# Communication_Interfaces.net
KiCad netlist of a schematic drawn in Altium Designer
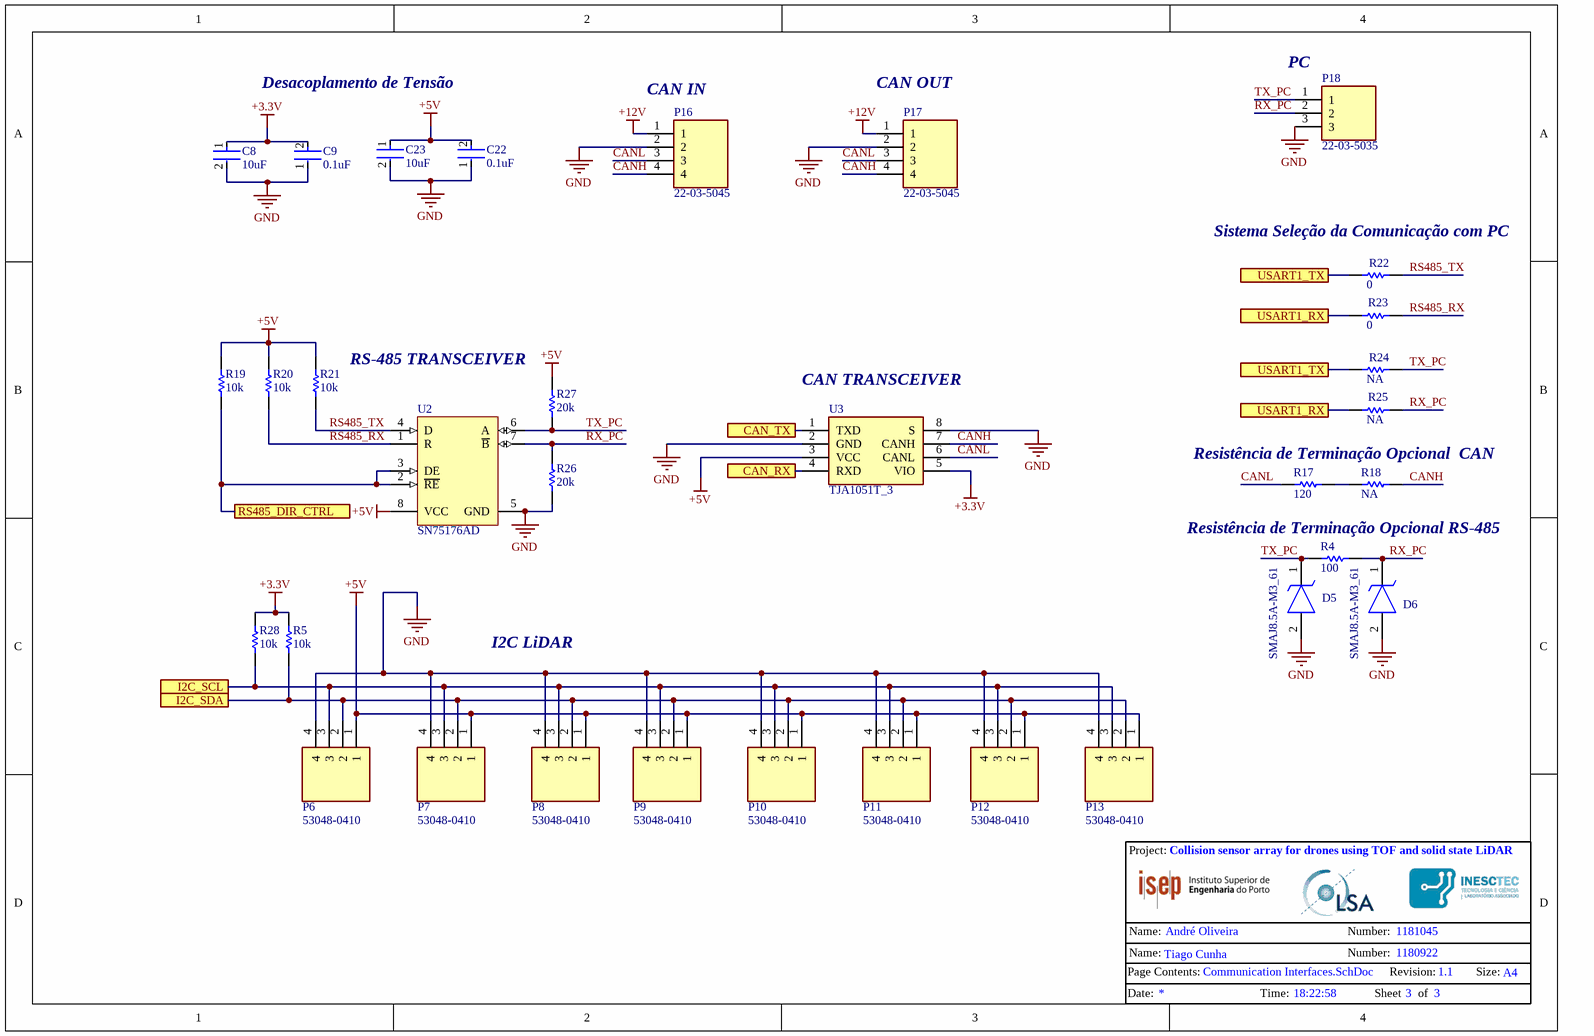
[diagram p0: Communication Interfaces.SchDoc]

(export (version "E")
  (design (tool "Eeschema 10.0.6"))
  (components
    (comp (ref "C8")
      (value "10uF")
      (footprint "FP-C3216-160-0_2-IPC_C")
      (description "Multilayer Ceramic Capacitors 10uF ±10% 16V X5R SMD 1206")
      (fields (field (name "VOLTAGE") "16V") (field (name "TOLERANCE") "10%"))
      (libsource (lib "Altium Content Vault") (part "11868f565c42a9108669ba33697ecf6"))
    )
    (comp (ref "C9")
      (value "0.1uF")
      (footprint "FP-GRM15-MFG")
      (description "CAP CER 0.1UF 16V X7R 0402")
      (fields (field (name "MANUFACTURER PART NUMBER") "GRM155R71C104KA88D") (field (name "TOLERANCE") "10%"))
      (libsource (lib "Altium Content Vault") (part "236180d848d6139a670b325ea6854c9"))
    )
    (comp (ref "C22")
      (value "0.1uF")
      (footprint "FP-GRM15-MFG")
      (description "CAP CER 0.1UF 16V X7R 0402")
      (fields (field (name "MANUFACTURER PART NUMBER") "GRM155R71C104KA88D") (field (name "TOLERANCE") "10%"))
      (libsource (lib "Altium Content Vault") (part "236180d848d6139a670b325ea6854c9"))
    )
    (comp (ref "C23")
      (value "10uF")
      (footprint "FP-C3216-160-0_2-IPC_C")
      (description "Multilayer Ceramic Capacitors 10uF ±10% 16V X5R SMD 1206")
      (fields (field (name "VOLTAGE") "16V") (field (name "TOLERANCE") "10%"))
      (libsource (lib "Altium Content Vault") (part "11868f565c42a9108669ba33697ecf6"))
    )
    (comp (ref "D5")
      (value "SMAJ8.5A-M3_61")
      (footprint "SamacSys:DIOM5127X229N")
      (description "TVS Diode (Uni-directional)")
      (fields (field (name "MANUFACTURER_PART_NUMBER") "SMAJ8.5A-M3/61"))
      (libsource (lib "*") (part "SMAJ8.5A-M3_61"))
    )
    (comp (ref "D6")
      (value "SMAJ8.5A-M3_61")
      (footprint "SamacSys:DIOM5127X229N")
      (description "TVS Diode (Uni-directional)")
      (fields (field (name "MANUFACTURER_PART_NUMBER") "SMAJ8.5A-M3/61"))
      (libsource (lib "*") (part "SMAJ8.5A-M3_61"))
    )
    (comp (ref "P6")
      (value "53048-0410")
      (footprint "SamacSys:530480410")
      (description "Connector")
      (fields (field (name "MOUSER PART NUMBER") "538-53048-0410"))
      (libsource (lib "*") (part "53048-0410"))
    )
    (comp (ref "P7")
      (value "53048-0410")
      (footprint "SamacSys:530480410")
      (description "Connector")
      (fields (field (name "MOUSER PART NUMBER") "538-53048-0410"))
      (libsource (lib "*") (part "53048-0410"))
    )
    (comp (ref "P8")
      (value "53048-0410")
      (footprint "SamacSys:530480410")
      (description "Connector")
      (fields (field (name "MOUSER PART NUMBER") "538-53048-0410"))
      (libsource (lib "*") (part "53048-0410"))
    )
    (comp (ref "P9")
      (value "53048-0410")
      (footprint "SamacSys:530480410")
      (description "Connector")
      (fields (field (name "MOUSER PART NUMBER") "538-53048-0410"))
      (libsource (lib "*") (part "53048-0410"))
    )
    (comp (ref "P10")
      (value "53048-0410")
      (footprint "SamacSys:530480410")
      (description "Connector")
      (fields (field (name "MOUSER PART NUMBER") "538-53048-0410"))
      (libsource (lib "*") (part "53048-0410"))
    )
    (comp (ref "P11")
      (value "53048-0410")
      (footprint "SamacSys:530480410")
      (description "Connector")
      (fields (field (name "MOUSER PART NUMBER") "538-53048-0410"))
      (libsource (lib "*") (part "53048-0410"))
    )
    (comp (ref "P12")
      (value "53048-0410")
      (footprint "SamacSys:530480410")
      (description "Connector")
      (fields (field (name "MOUSER PART NUMBER") "538-53048-0410"))
      (libsource (lib "*") (part "53048-0410"))
    )
    (comp (ref "P13")
      (value "53048-0410")
      (footprint "SamacSys:530480410")
      (description "Connector")
      (fields (field (name "MOUSER PART NUMBER") "538-53048-0410"))
      (libsource (lib "*") (part "53048-0410"))
    )
    (comp (ref "P16")
      (value "22-03-5045")
      (footprint "SamacSys:SHDR4W70P0X250_1X4_1240X490X610P")
      (description "Connector")
      (fields (field (name "MOUSER PART NUMBER") "538-22-03-5045"))
      (libsource (lib "*") (part "22-03-5045"))
    )
    (comp (ref "P17")
      (value "22-03-5045")
      (footprint "SamacSys:SHDR4W70P0X250_1X4_1240X490X610P")
      (description "Connector")
      (fields (field (name "MOUSER PART NUMBER") "538-22-03-5045"))
      (libsource (lib "*") (part "22-03-5045"))
    )
    (comp (ref "P18")
      (value "22-03-5035")
      (footprint "SamacSys:SHDR3W60P0X250_1X3_990X490X590P")
      (description "Connector")
      (fields (field (name "MOUSER PART NUMBER") "538-22-03-5035"))
      (libsource (lib "*") (part "22-03-5035"))
    )
    (comp (ref "R4")
      (value "100")
      (footprint "RESC1608X55X30ML20T20")
      (fields (field (name "MANUFACTURER") "Panasonic") (field (name "PART NUMBER") "ERA3AEB122V"))
      (libsource (lib "Altium Content Vault") (part "RES"))
    )
    (comp (ref "R5")
      (value "10k")
      (footprint "RESC1608X55X30ML20T20")
      (fields (field (name "MANUFACTURER") "Panasonic") (field (name "PART NUMBER") "ERA3AEB122V"))
      (libsource (lib "Altium Content Vault") (part "RES"))
    )
    (comp (ref "R17")
      (value "120")
      (footprint "RESC1608X55X30ML20T20")
      (fields (field (name "MANUFACTURER") "Panasonic") (field (name "PART NUMBER") "ERA3AEB122V"))
      (libsource (lib "Altium Content Vault") (part "RES"))
    )
    (comp (ref "R18")
      (value "NA")
      (footprint "RESC1608X55X30ML20T20")
      (fields (field (name "MANUFACTURER") "Panasonic") (field (name "PART NUMBER") "ERA3AEB122V"))
      (libsource (lib "Altium Content Vault") (part "RES"))
    )
    (comp (ref "R19")
      (value "10k")
      (footprint "RESC1608X55X30ML20T20")
      (fields (field (name "MANUFACTURER") "Panasonic") (field (name "PART NUMBER") "ERA3AEB122V"))
      (libsource (lib "Altium Content Vault") (part "RES"))
    )
    (comp (ref "R20")
      (value "10k")
      (footprint "RESC1608X55X30ML20T20")
      (fields (field (name "MANUFACTURER") "Panasonic") (field (name "PART NUMBER") "ERA3AEB122V"))
      (libsource (lib "Altium Content Vault") (part "RES"))
    )
    (comp (ref "R21")
      (value "10k")
      (footprint "RESC1608X55X30ML20T20")
      (fields (field (name "MANUFACTURER") "Panasonic") (field (name "PART NUMBER") "ERA3AEB122V"))
      (libsource (lib "Altium Content Vault") (part "RES"))
    )
    (comp (ref "R22")
      (value "0")
      (footprint "RESC1608X55X30ML20T20")
      (fields (field (name "MANUFACTURER") "Panasonic") (field (name "PART NUMBER") "ERA3AEB122V"))
      (libsource (lib "Altium Content Vault") (part "RES"))
    )
    (comp (ref "R23")
      (value "0")
      (footprint "RESC1608X55X30ML20T20")
      (fields (field (name "MANUFACTURER") "Panasonic") (field (name "PART NUMBER") "ERA3AEB122V"))
      (libsource (lib "Altium Content Vault") (part "RES"))
    )
    (comp (ref "R24")
      (value "NA")
      (footprint "RESC1608X55X30ML20T20")
      (fields (field (name "MANUFACTURER") "Panasonic") (field (name "PART NUMBER") "ERA3AEB122V"))
      (libsource (lib "Altium Content Vault") (part "RES"))
    )
    (comp (ref "R25")
      (value "NA")
      (footprint "RESC1608X55X30ML20T20")
      (fields (field (name "MANUFACTURER") "Panasonic") (field (name "PART NUMBER") "ERA3AEB122V"))
      (libsource (lib "Altium Content Vault") (part "RES"))
    )
    (comp (ref "R26")
      (value "20k")
      (footprint "RESC1608X55X30ML20T20")
      (fields (field (name "MANUFACTURER") "Panasonic") (field (name "PART NUMBER") "ERA3AEB122V"))
      (libsource (lib "Altium Content Vault") (part "RES"))
    )
    (comp (ref "R27")
      (value "20k")
      (footprint "RESC1608X55X30ML20T20")
      (fields (field (name "MANUFACTURER") "Panasonic") (field (name "PART NUMBER") "ERA3AEB122V"))
      (libsource (lib "Altium Content Vault") (part "RES"))
    )
    (comp (ref "R28")
      (value "10k")
      (footprint "RESC1608X55X30ML20T20")
      (fields (field (name "MANUFACTURER") "Panasonic") (field (name "PART NUMBER") "ERA3AEB122V"))
      (libsource (lib "Altium Content Vault") (part "RES"))
    )
    (comp (ref "U2")
      (value "SN75176AD")
      (footprint "D0008A_M")
      (fields (field (name "MANUFACTURER") "Texas Instruments"))
      (libsource (lib "Altium Content Vault") (part "TI-SN75176A-SOIC_D-8"))
    )
    (comp (ref "U3")
      (value "TJA1051T_3")
      (footprint "SamacSys:SOIC127P600X175-8N")
      (description "Integrated Circuit")
      (fields
        (field (name "MANUFACTURER_PART_NUMBER") "TJA1051T/3/CM,118")
        (field (name "MOUSER PART NUMBER") "771-TJA1051T/3CM118")
      )
      (libsource (lib "SamacSys") (part "TJA1051T_3_CM,118"))
    )
  )
  (nets
    (net (code "1") (name "+3.3V") (class "Default")
      (node (ref "C8") (pin "1") (pinfunction "1_1") (pintype "passive"))
      (node (ref "C9") (pin "2") (pinfunction "2_2") (pintype "passive"))
      (node (ref "R28") (pin "2") (pinfunction "2_2") (pintype "passive"))
      (node (ref "R5") (pin "2") (pinfunction "2_2") (pintype "passive"))
      (node (ref "U3") (pin "5") (pinfunction "VIO_5") (pintype "passive"))
    )
    (net (code "2") (name "+5V") (class "Default")
      (node (ref "C22") (pin "2") (pinfunction "2_2") (pintype "passive"))
      (node (ref "C23") (pin "1") (pinfunction "1_1") (pintype "passive"))
      (node (ref "P10") (pin "1") (pinfunction "1_1") (pintype "passive"))
      (node (ref "P11") (pin "1") (pinfunction "1_1") (pintype "passive"))
      (node (ref "P12") (pin "1") (pinfunction "1_1") (pintype "passive"))
      (node (ref "P13") (pin "1") (pinfunction "1_1") (pintype "passive"))
      (node (ref "P6") (pin "1") (pinfunction "1_1") (pintype "passive"))
      (node (ref "P7") (pin "1") (pinfunction "1_1") (pintype "passive"))
      (node (ref "P8") (pin "1") (pinfunction "1_1") (pintype "passive"))
      (node (ref "P9") (pin "1") (pinfunction "1_1") (pintype "passive"))
      (node (ref "R19") (pin "2") (pinfunction "2_2") (pintype "passive"))
      (node (ref "R20") (pin "2") (pinfunction "2_2") (pintype "passive"))
      (node (ref "R21") (pin "2") (pinfunction "2_2") (pintype "passive"))
      (node (ref "R27") (pin "1") (pinfunction "1_1") (pintype "passive"))
      (node (ref "U2") (pin "8") (pinfunction "VCC_8") (pintype "power_in"))
      (node (ref "U3") (pin "3") (pinfunction "VCC_3") (pintype "power_in"))
    )
    (net (code "3") (name "+12V") (class "Default")
      (node (ref "P16") (pin "1") (pinfunction "1_1") (pintype "passive"))
      (node (ref "P17") (pin "1") (pinfunction "1_1") (pintype "passive"))
    )
    (net (code "4") (name "/CANH") (class "Default")
      (node (ref "P16") (pin "4") (pinfunction "4_4") (pintype "passive"))
      (node (ref "P17") (pin "4") (pinfunction "4_4") (pintype "passive"))
      (node (ref "R18") (pin "1") (pinfunction "1_1") (pintype "passive"))
      (node (ref "U3") (pin "7") (pinfunction "CANH_7") (pintype "passive"))
    )
    (net (code "5") (name "/CANL") (class "Default")
      (node (ref "P16") (pin "3") (pinfunction "3_3") (pintype "passive"))
      (node (ref "P17") (pin "3") (pinfunction "3_3") (pintype "passive"))
      (node (ref "R17") (pin "2") (pinfunction "2_2") (pintype "passive"))
      (node (ref "U3") (pin "6") (pinfunction "CANL_6") (pintype "passive"))
    )
    (net (code "6") (name "/CAN_RX") (class "Default")
      (node (ref "U3") (pin "4") (pinfunction "RXD_4") (pintype "passive"))
    )
    (net (code "7") (name "/CAN_TX") (class "Default")
      (node (ref "U3") (pin "1") (pinfunction "TXD_1") (pintype "passive"))
    )
    (net (code "8") (name "/I2C_SCL") (class "Default")
      (node (ref "P10") (pin "3") (pinfunction "3_3") (pintype "passive"))
      (node (ref "P11") (pin "3") (pinfunction "3_3") (pintype "passive"))
      (node (ref "P12") (pin "3") (pinfunction "3_3") (pintype "passive"))
      (node (ref "P13") (pin "3") (pinfunction "3_3") (pintype "passive"))
      (node (ref "P6") (pin "3") (pinfunction "3_3") (pintype "passive"))
      (node (ref "P7") (pin "3") (pinfunction "3_3") (pintype "passive"))
      (node (ref "P8") (pin "3") (pinfunction "3_3") (pintype "passive"))
      (node (ref "P9") (pin "3") (pinfunction "3_3") (pintype "passive"))
      (node (ref "R28") (pin "1") (pinfunction "1_1") (pintype "passive"))
    )
    (net (code "9") (name "/I2C_SDA") (class "Default")
      (node (ref "P10") (pin "2") (pinfunction "2_2") (pintype "passive"))
      (node (ref "P11") (pin "2") (pinfunction "2_2") (pintype "passive"))
      (node (ref "P12") (pin "2") (pinfunction "2_2") (pintype "passive"))
      (node (ref "P13") (pin "2") (pinfunction "2_2") (pintype "passive"))
      (node (ref "P6") (pin "2") (pinfunction "2_2") (pintype "passive"))
      (node (ref "P7") (pin "2") (pinfunction "2_2") (pintype "passive"))
      (node (ref "P8") (pin "2") (pinfunction "2_2") (pintype "passive"))
      (node (ref "P9") (pin "2") (pinfunction "2_2") (pintype "passive"))
      (node (ref "R5") (pin "1") (pinfunction "1_1") (pintype "passive"))
    )
    (net (code "10") (name "/RS485_DIR_CTRL") (class "Default")
      (node (ref "R19") (pin "1") (pinfunction "1_1") (pintype "passive"))
      (node (ref "U2") (pin "2") (pinfunction "~{RE}_2") (pintype "input"))
      (node (ref "U2") (pin "3") (pinfunction "DE_3") (pintype "input"))
    )
    (net (code "11") (name "/RS485_RX") (class "Default")
      (node (ref "R20") (pin "1") (pinfunction "1_1") (pintype "passive"))
      (node (ref "R23") (pin "1") (pinfunction "1_1") (pintype "passive"))
      (node (ref "U2") (pin "1") (pinfunction "R_1") (pintype "tri_state"))
    )
    (net (code "12") (name "/RS485_TX") (class "Default")
      (node (ref "R21") (pin "1") (pinfunction "1_1") (pintype "passive"))
      (node (ref "R22") (pin "1") (pinfunction "1_1") (pintype "passive"))
      (node (ref "U2") (pin "4") (pinfunction "D_4") (pintype "input"))
    )
    (net (code "13") (name "/RX_PC") (class "Default")
      (node (ref "D6") (pin "1") (pinfunction "K_1") (pintype "passive"))
      (node (ref "P18") (pin "2") (pinfunction "2_2") (pintype "passive"))
      (node (ref "R25") (pin "1") (pinfunction "1_1") (pintype "passive"))
      (node (ref "R26") (pin "1") (pinfunction "1_1") (pintype "passive"))
      (node (ref "R4") (pin "1") (pinfunction "1_1") (pintype "passive"))
      (node (ref "U2") (pin "7") (pinfunction "~{B}_7") (pintype "bidirectional"))
    )
    (net (code "14") (name "/TX_PC") (class "Default")
      (node (ref "D5") (pin "1") (pinfunction "K_1") (pintype "passive"))
      (node (ref "P18") (pin "1") (pinfunction "1_1") (pintype "passive"))
      (node (ref "R24") (pin "1") (pinfunction "1_1") (pintype "passive"))
      (node (ref "R27") (pin "2") (pinfunction "2_2") (pintype "passive"))
      (node (ref "R4") (pin "2") (pinfunction "2_2") (pintype "passive"))
      (node (ref "U2") (pin "6") (pinfunction "A_6") (pintype "bidirectional"))
    )
    (net (code "15") (name "/USART1_RX") (class "Default")
      (node (ref "R23") (pin "2") (pinfunction "2_2") (pintype "passive"))
      (node (ref "R25") (pin "2") (pinfunction "2_2") (pintype "passive"))
    )
    (net (code "16") (name "/USART1_TX") (class "Default")
      (node (ref "R22") (pin "2") (pinfunction "2_2") (pintype "passive"))
      (node (ref "R24") (pin "2") (pinfunction "2_2") (pintype "passive"))
    )
    (net (code "17") (name "GND") (class "Default")
      (node (ref "C22") (pin "1") (pinfunction "1_1") (pintype "passive"))
      (node (ref "C23") (pin "2") (pinfunction "2_2") (pintype "passive"))
      (node (ref "C8") (pin "2") (pinfunction "2_2") (pintype "passive"))
      (node (ref "C9") (pin "1") (pinfunction "1_1") (pintype "passive"))
      (node (ref "D5") (pin "2") (pinfunction "A_2") (pintype "passive"))
      (node (ref "D6") (pin "2") (pinfunction "A_2") (pintype "passive"))
      (node (ref "P10") (pin "4") (pinfunction "4_4") (pintype "passive"))
      (node (ref "P11") (pin "4") (pinfunction "4_4") (pintype "passive"))
      (node (ref "P12") (pin "4") (pinfunction "4_4") (pintype "passive"))
      (node (ref "P13") (pin "4") (pinfunction "4_4") (pintype "passive"))
      (node (ref "P16") (pin "2") (pinfunction "2_2") (pintype "passive"))
      (node (ref "P17") (pin "2") (pinfunction "2_2") (pintype "passive"))
      (node (ref "P18") (pin "3") (pinfunction "3_3") (pintype "passive"))
      (node (ref "P6") (pin "4") (pinfunction "4_4") (pintype "passive"))
      (node (ref "P7") (pin "4") (pinfunction "4_4") (pintype "passive"))
      (node (ref "P8") (pin "4") (pinfunction "4_4") (pintype "passive"))
      (node (ref "P9") (pin "4") (pinfunction "4_4") (pintype "passive"))
      (node (ref "R26") (pin "2") (pinfunction "2_2") (pintype "passive"))
      (node (ref "U2") (pin "5") (pinfunction "GND_5") (pintype "power_in"))
      (node (ref "U3") (pin "2") (pinfunction "GND_2") (pintype "power_in"))
      (node (ref "U3") (pin "8") (pinfunction "S_8") (pintype "passive"))
    )
    (net (code "18") (name "Net-(R17-Pad1)") (class "Default")
      (node (ref "R17") (pin "1") (pinfunction "1_1") (pintype "passive"))
      (node (ref "R18") (pin "2") (pinfunction "2_2") (pintype "passive"))
    )
  )
)
